# power.net
KiCad netlist of a schematic drawn in Altium Designer
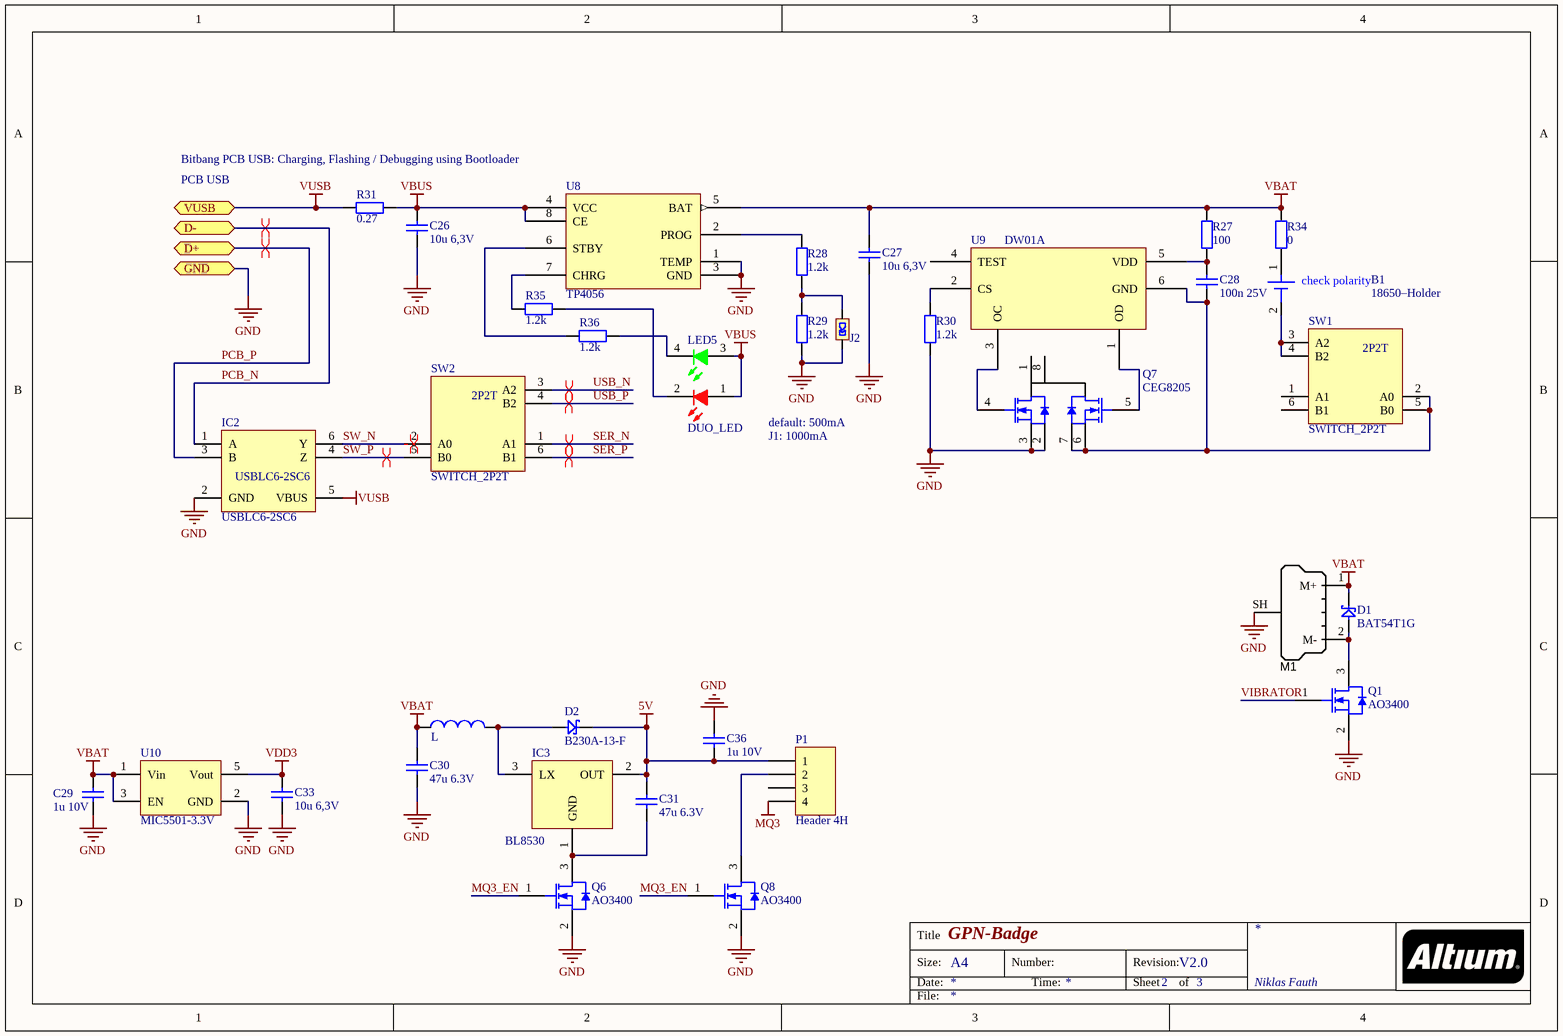
[diagram p0: power.SchDoc]

(export (version "E")
  (design (tool "Eeschema 10.0.6"))
  (components
    (comp (ref "*") (value "L") (footprint "L") (libsource (lib "gpn-badge") (part "L")))
    (comp (ref "B1")
      (value "18650–Holder")
      (footprint "18650–Holder-SMD")
      (libsource (lib "gpn-badge") (part "18650–Holder"))
    )
    (comp (ref "C26")
      (value "10u 6,3V")
      (footprint "C-0603-H")
      (description "Capacitor 10uF 6,3V")
      (libsource (lib "Passives") (part "C-0603-10u-6,3V"))
    )
    (comp (ref "C27")
      (value "10u 6,3V")
      (footprint "C-0603-H")
      (description "Capacitor 10uF 6,3V")
      (libsource (lib "Passives") (part "C-0603-10u-6,3V"))
    )
    (comp (ref "C28")
      (value "100n 25V")
      (footprint "C-0603-M")
      (description "Capacitor 100n 25V")
      (libsource (lib "Passives") (part "C-0603-100n-25V"))
    )
    (comp (ref "C29")
      (value "1u 10V")
      (footprint "C-0603-M")
      (description "Capacitor 1uF 10V")
      (libsource (lib "Passives") (part "C-0603-1u-10V"))
    )
    (comp (ref "C30")
      (value "47u 6.3V")
      (footprint "C-0805-M")
      (description "Capacitor 47u 6.3V")
      (libsource (lib "Passives") (part "C-0805-47u-6.3V"))
    )
    (comp (ref "C31")
      (value "47u 6.3V")
      (footprint "C-0805-M")
      (description "Capacitor 47u 6.3V")
      (libsource (lib "Passives") (part "C-0805-47u-6.3V"))
    )
    (comp (ref "C33")
      (value "10u 6,3V")
      (footprint "C-0603-H")
      (description "Capacitor 10uF 6,3V")
      (libsource (lib "Passives") (part "C-0603-10u-6,3V"))
    )
    (comp (ref "C36")
      (value "1u 10V")
      (footprint "C-0603-M")
      (description "Capacitor 1uF 10V")
      (libsource (lib "Passives") (part "C-0603-1u-10V"))
    )
    (comp (ref "D1") (value "BAT54T1G") (footprint "SOD123") (libsource (lib "advanced") (part "D-BAT54T1G")))
    (comp (ref "D2")
      (value "B230A-13-F")
      (footprint "DIODE-SMA")
      (libsource (lib "advanced") (part "D-B230A-13-F"))
    )
    (comp (ref "IC2")
      (value "USBLC6-2SC6")
      (footprint "SOT23-6")
      (description "USB protection")
      (libsource (lib "gpn-badge") (part "USBLC6-2SC6"))
    )
    (comp (ref "IC3")
      (value "BL8530")
      (footprint "SOT89-150P409X160-3N")
      (libsource (lib "gpn-badge") (part "BL8530"))
    )
    (comp (ref "J2")
      (value "jumper")
      (footprint "JUMPER 1-1")
      (libsource (lib "advanced") (part "jumper 1-1"))
    )
    (comp (ref "LED5") (value "DUO_LED") (footprint "LEDDUO") (libsource (lib "gpn-badge") (part "DUO_LED")))
    (comp (ref "M1")
      (value "VIBRATOR")
      (footprint "VIBRATOR_SMD")
      (description "rawr")
      (libsource (lib "gpn-badge") (part "VIBRATOR"))
    )
    (comp (ref "P1")
      (value "Header 4H")
      (footprint "HDR1X4H")
      (description "Header, 4-Pin, Right Angle")
      (fields (field (name "PUBLISHER") "Altium Limited"))
      (libsource (lib "Miscellaneous Connectors") (part "Header 4H"))
    )
    (comp (ref "Q1")
      (value "AO3400")
      (footprint "AO-SOT23-3_V")
      (description "N-channel Enhancement Mode Field-Effect Transistor; 5.8A/30V")
      (fields (field (name "MANUFACTURER") "Alpha and Omega"))
      (libsource (lib "Altium Content Vault") (part "AO-NEMOS-G1S2D3-3"))
    )
    (comp (ref "Q6")
      (value "AO3400")
      (footprint "AO-SOT23-3_V")
      (description "N-channel Enhancement Mode Field-Effect Transistor; 5.8A/30V")
      (fields (field (name "MANUFACTURER") "Alpha and Omega"))
      (libsource (lib "Altium Content Vault") (part "AO-NEMOS-G1S2D3-3"))
    )
    (comp (ref "Q7")
      (value "CEG8205")
      (footprint "SOP64P640X265-8N")
      (description "Dual mini mosfet 20V 4.5A")
      (libsource (lib "gpn-badge") (part "MOSFET-CEG8205"))
    )
    (comp (ref "Q8")
      (value "AO3400")
      (footprint "AO-SOT23-3_V")
      (description "N-channel Enhancement Mode Field-Effect Transistor; 5.8A/30V")
      (fields (field (name "MANUFACTURER") "Alpha and Omega"))
      (libsource (lib "Altium Content Vault") (part "AO-NEMOS-G1S2D3-3"))
    )
    (comp (ref "R27")
      (value "100")
      (footprint "R-0603-M")
      (description "Resistor 100")
      (libsource (lib "Passives") (part "R-0603-100"))
    )
    (comp (ref "R28")
      (value "1.2k")
      (footprint "R-0603-M")
      (description "Resistor 1.2k")
      (libsource (lib "") (part "R-0603-1k2_1"))
    )
    (comp (ref "R29")
      (value "1.2k")
      (footprint "R-0603-M")
      (description "Resistor 1.2k")
      (libsource (lib "") (part "R-0603-1k2_1"))
    )
    (comp (ref "R30")
      (value "1.2k")
      (footprint "R-0603-M")
      (description "Resistor 1.2k")
      (libsource (lib "") (part "R-0603-1k2_1"))
    )
    (comp (ref "R31")
      (value "0.27")
      (footprint "R-1206-M")
      (description "Resistor 0.27")
      (libsource (lib "Passives") (part "R-1206-0R27"))
    )
    (comp (ref "R34")
      (value "0")
      (footprint "R-0603-M")
      (description "Resistor 0")
      (libsource (lib "Passives") (part "R-0603-0"))
    )
    (comp (ref "R35")
      (value "1.2k")
      (footprint "R-0603-M")
      (description "Resistor 1.2k")
      (libsource (lib "Passives") (part "R-0603-1k2"))
    )
    (comp (ref "R36")
      (value "1.2k")
      (footprint "R-0603-M")
      (description "Resistor 1.2k")
      (libsource (lib "Passives") (part "R-0603-1k2"))
    )
    (comp (ref "SW1")
      (value "SWITCH_2P2T")
      (footprint "SWITCH_THT")
      (libsource (lib "gpn-badge") (part "SWITCH_2P2T"))
    )
    (comp (ref "SW2")
      (value "SWITCH_2P2T")
      (footprint "SWITCH_THT")
      (libsource (lib "") (part "SWITCH_2P2T_1"))
    )
    (comp (ref "U8")
      (value "TP4056")
      (footprint "SOIC127P600X20_HS-9N")
      (description "1A standalone linear charging IC")
      (libsource (lib "advanced") (part "TP4056"))
    )
    (comp (ref "U9")
      (value "DW01A")
      (footprint "SOT23-6")
      (description "Single Cell LiIon LiPo Protection")
      (libsource (lib "advanced") (part "DW01A"))
    )
    (comp (ref "U10")
      (value "MIC5501-3.3V")
      (footprint "SOT23-5")
      (libsource (lib "advanced") (part "MIC5501-3.3V"))
    )
  )
  (nets
    (net (code "1") (name "/MQ3_EN") (class "Default")
      (node (ref "Q6") (pin "1") (pinfunction "G_1") (pintype "passive"))
      (node (ref "Q8") (pin "1") (pinfunction "G_1") (pintype "passive"))
    )
    (net (code "2") (name "/PCB_N") (class "Default")
      (node (ref "IC2") (pin "1") (pinfunction "A_1") (pintype "passive"))
    )
    (net (code "3") (name "/PCB_P") (class "Default")
      (node (ref "IC2") (pin "3") (pinfunction "B_3") (pintype "passive"))
    )
    (net (code "4") (name "/SER_N") (class "Default")
      (node (ref "SW2") (pin "1") (pinfunction "A1_1") (pintype "passive"))
    )
    (net (code "5") (name "/SER_P") (class "Default")
      (node (ref "SW2") (pin "6") (pinfunction "B1_6") (pintype "passive"))
    )
    (net (code "6") (name "/SW_N") (class "Default")
      (node (ref "IC2") (pin "6") (pinfunction "Y_6") (pintype "passive"))
      (node (ref "SW2") (pin "2") (pinfunction "A0_2") (pintype "passive"))
    )
    (net (code "7") (name "/SW_P") (class "Default")
      (node (ref "IC2") (pin "4") (pinfunction "Z_4") (pintype "passive"))
      (node (ref "SW2") (pin "5") (pinfunction "B0_5") (pintype "passive"))
    )
    (net (code "8") (name "/USB_N") (class "Default")
      (node (ref "SW2") (pin "3") (pinfunction "A2_3") (pintype "passive"))
    )
    (net (code "9") (name "/USB_P") (class "Default")
      (node (ref "SW2") (pin "4") (pinfunction "B2_4") (pintype "passive"))
    )
    (net (code "10") (name "/VIBRATOR") (class "Default")
      (node (ref "Q1") (pin "1") (pinfunction "G_1") (pintype "passive"))
    )
    (net (code "11") (name "5V") (class "Default")
      (node (ref "C31") (pin "2") (pinfunction "2_2") (pintype "passive"))
      (node (ref "C36") (pin "2") (pinfunction "2_2") (pintype "passive"))
      (node (ref "D2") (pin "2") (pinfunction "kt_2") (pintype "passive"))
      (node (ref "IC3") (pin "2") (pinfunction "OUT_2") (pintype "passive"))
      (node (ref "P1") (pin "1") (pinfunction "1_1") (pintype "passive"))
    )
    (net (code "12") (name "GND") (class "Default")
      (node (ref "C26") (pin "1") (pinfunction "1_1") (pintype "passive"))
      (node (ref "C27") (pin "1") (pinfunction "1_1") (pintype "passive"))
      (node (ref "C29") (pin "1") (pinfunction "1_1") (pintype "passive"))
      (node (ref "C30") (pin "1") (pinfunction "1_1") (pintype "passive"))
      (node (ref "C33") (pin "1") (pinfunction "1_1") (pintype "passive"))
      (node (ref "C36") (pin "1") (pinfunction "1_1") (pintype "passive"))
      (node (ref "IC2") (pin "2") (pinfunction "GND_2") (pintype "passive"))
      (node (ref "J2") (pin "2") (pintype "passive"))
      (node (ref "M1") (pin "SH") (pinfunction "Shell_SH") (pintype "passive"))
      (node (ref "Q1") (pin "2") (pinfunction "S_2") (pintype "passive"))
      (node (ref "Q6") (pin "2") (pinfunction "S_2") (pintype "passive"))
      (node (ref "Q7") (pin "2") (pinfunction "S1_2") (pintype "passive"))
      (node (ref "Q7") (pin "3") (pinfunction "S1_3") (pintype "passive"))
      (node (ref "Q8") (pin "2") (pinfunction "S_2") (pintype "passive"))
      (node (ref "R29") (pin "1") (pinfunction "1_1") (pintype "passive"))
      (node (ref "R30") (pin "1") (pinfunction "1_1") (pintype "passive"))
      (node (ref "U10") (pin "2") (pinfunction "GND_2") (pintype "passive"))
      (node (ref "U8") (pin "1") (pinfunction "TEMP_1") (pintype "passive"))
      (node (ref "U8") (pin "3") (pinfunction "GND_3") (pintype "power_in"))
    )
    (net (code "13") (name "MQ3") (class "Default")
      (node (ref "P1") (pin "4") (pinfunction "4_4") (pintype "passive"))
    )
    (net (code "14") (name "Net-(B1-Pad1)") (class "Default")
      (node (ref "B1") (pin "1") (pintype "passive"))
      (node (ref "R34") (pin "1") (pinfunction "1_1") (pintype "passive"))
    )
    (net (code "15") (name "Net-(D1-an)") (class "Default")
      (node (ref "D1") (pin "1") (pinfunction "an_1") (pintype "passive"))
      (node (ref "M1") (pin "2") (pinfunction "M-_2") (pintype "passive"))
      (node (ref "Q1") (pin "3") (pinfunction "D_3") (pintype "passive"))
    )
    (net (code "16") (name "Net-(D2-an)") (class "Default")
      (node (ref "*") (pin "2") (pinfunction "2_2") (pintype "passive"))
      (node (ref "D2") (pin "1") (pinfunction "an_1") (pintype "passive"))
      (node (ref "IC3") (pin "3") (pinfunction "LX_3") (pintype "passive"))
    )
    (net (code "17") (name "Net-(IC3-GND)") (class "Default")
      (node (ref "C31") (pin "1") (pinfunction "1_1") (pintype "passive"))
      (node (ref "IC3") (pin "1") (pinfunction "GND_1") (pintype "passive"))
      (node (ref "Q6") (pin "3") (pinfunction "D_3") (pintype "passive"))
    )
    (net (code "18") (name "Net-(J2-Pad1)") (class "Default")
      (node (ref "J2") (pin "1") (pintype "passive"))
      (node (ref "R28") (pin "1") (pinfunction "1_1") (pintype "passive"))
      (node (ref "R29") (pin "2") (pinfunction "2_2") (pintype "passive"))
    )
    (net (code "19") (name "Net-(LED5-K-Pad2)") (class "Default")
      (node (ref "LED5") (pin "2") (pinfunction "K_2") (pintype "passive"))
      (node (ref "R35") (pin "1") (pinfunction "1_1") (pintype "passive"))
    )
    (net (code "20") (name "Net-(LED5-K-Pad4)") (class "Default")
      (node (ref "LED5") (pin "4") (pinfunction "K_4") (pintype "passive"))
      (node (ref "R36") (pin "1") (pinfunction "1_1") (pintype "passive"))
    )
    (net (code "21") (name "Net-(Q7-G1)") (class "Default")
      (node (ref "Q7") (pin "4") (pinfunction "G1_4") (pintype "passive"))
      (node (ref "U9") (pin "3") (pinfunction "OC_3") (pintype "passive"))
    )
    (net (code "22") (name "Net-(Q7-G2)") (class "Default")
      (node (ref "Q7") (pin "5") (pinfunction "G2_5") (pintype "passive"))
      (node (ref "U9") (pin "1") (pinfunction "OD_1") (pintype "passive"))
    )
    (net (code "23") (name "Net-(Q8-D)") (class "Default")
      (node (ref "P1") (pin "2") (pinfunction "2_2") (pintype "passive"))
      (node (ref "Q8") (pin "3") (pinfunction "D_3") (pintype "passive"))
    )
    (net (code "24") (name "Net-(SW1-A0)") (class "Default")
      (node (ref "C28") (pin "1") (pinfunction "1_1") (pintype "passive"))
      (node (ref "Q7") (pin "6") (pinfunction "S2_6") (pintype "passive"))
      (node (ref "Q7") (pin "7") (pinfunction "S2_7") (pintype "passive"))
      (node (ref "SW1") (pin "2") (pinfunction "A0_2") (pintype "passive"))
      (node (ref "SW1") (pin "5") (pinfunction "B0_5") (pintype "passive"))
      (node (ref "U9") (pin "6") (pinfunction "GND_6") (pintype "passive"))
    )
    (net (code "25") (name "Net-(SW1-A2)") (class "Default")
      (node (ref "B1") (pin "2") (pintype "passive"))
      (node (ref "SW1") (pin "3") (pinfunction "A2_3") (pintype "passive"))
      (node (ref "SW1") (pin "4") (pinfunction "B2_4") (pintype "passive"))
    )
    (net (code "26") (name "Net-(U8-CHRG)") (class "Default")
      (node (ref "R35") (pin "2") (pinfunction "2_2") (pintype "passive"))
      (node (ref "U8") (pin "7") (pinfunction "CHRG_7") (pintype "passive"))
    )
    (net (code "27") (name "Net-(U8-PROG)") (class "Default")
      (node (ref "R28") (pin "2") (pinfunction "2_2") (pintype "passive"))
      (node (ref "U8") (pin "2") (pinfunction "PROG_2") (pintype "passive"))
    )
    (net (code "28") (name "Net-(U8-STBY)") (class "Default")
      (node (ref "R36") (pin "2") (pinfunction "2_2") (pintype "passive"))
      (node (ref "U8") (pin "6") (pinfunction "STBY_6") (pintype "passive"))
    )
    (net (code "29") (name "Net-(U9-CS)") (class "Default")
      (node (ref "R30") (pin "2") (pinfunction "2_2") (pintype "passive"))
      (node (ref "U9") (pin "2") (pinfunction "CS_2") (pintype "passive"))
    )
    (net (code "30") (name "Net-(U9-VDD)") (class "Default")
      (node (ref "C28") (pin "2") (pinfunction "2_2") (pintype "passive"))
      (node (ref "R27") (pin "1") (pinfunction "1_1") (pintype "passive"))
      (node (ref "U9") (pin "5") (pinfunction "VDD_5") (pintype "passive"))
    )
    (net (code "31") (name "VBAT") (class "Default")
      (node (ref "*") (pin "1") (pinfunction "1_1") (pintype "passive"))
      (node (ref "C27") (pin "2") (pinfunction "2_2") (pintype "passive"))
      (node (ref "C29") (pin "2") (pinfunction "2_2") (pintype "passive"))
      (node (ref "C30") (pin "2") (pinfunction "2_2") (pintype "passive"))
      (node (ref "D1") (pin "2") (pinfunction "kt_2") (pintype "passive"))
      (node (ref "M1") (pin "1") (pinfunction "M+_1") (pintype "passive"))
      (node (ref "R27") (pin "2") (pinfunction "2_2") (pintype "passive"))
      (node (ref "R34") (pin "2") (pinfunction "2_2") (pintype "passive"))
      (node (ref "U10") (pin "1") (pinfunction "Vin_1") (pintype "passive"))
      (node (ref "U10") (pin "3") (pinfunction "EN_3") (pintype "passive"))
      (node (ref "U8") (pin "5") (pinfunction "BAT_5") (pintype "output"))
    )
    (net (code "32") (name "VBUS") (class "Default")
      (node (ref "C26") (pin "2") (pinfunction "2_2") (pintype "passive"))
      (node (ref "LED5") (pin "1") (pinfunction "A_1") (pintype "passive"))
      (node (ref "LED5") (pin "3") (pinfunction "A_3") (pintype "passive"))
      (node (ref "R31") (pin "2") (pinfunction "2_2") (pintype "passive"))
      (node (ref "U8") (pin "4") (pinfunction "VCC_4") (pintype "passive"))
      (node (ref "U8") (pin "8") (pinfunction "CE_8") (pintype "passive"))
    )
    (net (code "33") (name "VDD3") (class "Default")
      (node (ref "C33") (pin "2") (pinfunction "2_2") (pintype "passive"))
      (node (ref "U10") (pin "5") (pinfunction "Vout_5") (pintype "passive"))
    )
    (net (code "34") (name "VUSB") (class "Default")
      (node (ref "IC2") (pin "5") (pinfunction "VBUS_5") (pintype "passive"))
      (node (ref "R31") (pin "1") (pinfunction "1_1") (pintype "passive"))
    )
    (net (code "35") (name "unconnected-(P1-Pad3)") (class "Default")
      (node (ref "P1") (pin "3") (pinfunction "3_3") (pintype "passive"))
    )
    (net (code "36") (name "unconnected-(Q7-D-Pad8)") (class "Default")
      (node (ref "Q7") (pin "8") (pinfunction "D_8") (pintype "passive"))
    )
    (net (code "37") (name "unconnected-(Q7-S-Pad1)") (class "Default")
      (node (ref "Q7") (pin "1") (pinfunction "S_1") (pintype "passive"))
    )
    (net (code "38") (name "unconnected-(SW1-A1-Pad1)") (class "Default")
      (node (ref "SW1") (pin "1") (pinfunction "A1_1") (pintype "passive"))
    )
    (net (code "39") (name "unconnected-(SW1-B1-Pad6)") (class "Default")
      (node (ref "SW1") (pin "6") (pinfunction "B1_6") (pintype "passive"))
    )
    (net (code "40") (name "unconnected-(U9-TEST-Pad4)") (class "Default")
      (node (ref "U9") (pin "4") (pinfunction "TEST_4") (pintype "passive"))
    )
  )
)
